# TEMPIC.net
KiCad netlist of a schematic drawn in Altium Designer
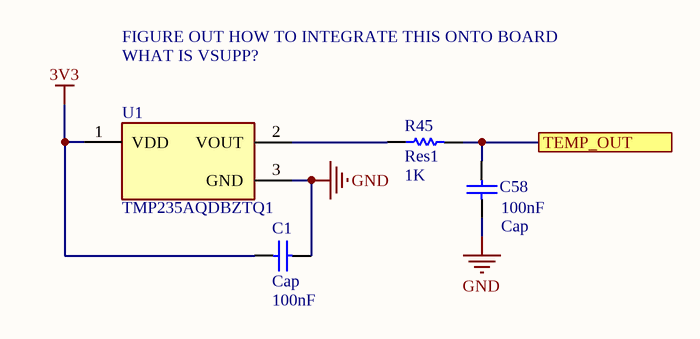
[diagram p0: TEMPIC.SchDoc]

(export (version "E")
  (design (tool "Eeschema 10.0.6"))
  (components
    (comp (ref "C1")
      (value "Cap")
      (footprint "0402")
      (description "Capacitor")
      (fields (field (name "ALTIUM_VALUE") "100nF") (field (name "PUBLISHER") "Altium Limited"))
      (libsource (lib "Miscellaneous Devices") (part "Cap"))
    )
    (comp (ref "C58")
      (value "Cap")
      (footprint "0402")
      (description "Capacitor")
      (fields (field (name "ALTIUM_VALUE") "100nF") (field (name "PUBLISHER") "Altium Limited"))
      (libsource (lib "Miscellaneous Devices") (part "Cap"))
    )
    (comp (ref "R45")
      (value "Res1")
      (footprint "0402")
      (description "Resistor")
      (fields (field (name "ALTIUM_VALUE") "1K") (field (name "PUBLISHER") "Altium Limited"))
      (libsource (lib "Miscellaneous Devices") (part "Res1"))
    )
    (comp (ref "U1")
      (value "TMP235AQDBZTQ1")
      (footprint "FP-DBZ0003A-MFG")
      (description "LOW-POWER HIGH-ACCURACY ANALOG O")
      (fields
        (field (name "MANUFACTURER") "Texas Instruments")
        (field (name "MANUFACTURER PART NUMBER") "TMP235A2DBZR")
      )
      (libsource (lib "Altium Content Vault") (part "1212246baba8f64ab0dd7b63bd818eb"))
    )
  )
  (nets
    (net (code "1") (name "/TEMP_OUT") (class "Default")
      (node (ref "C58") (pin "1") (pinfunction "1_1") (pintype "passive"))
      (node (ref "R45") (pin "2") (pinfunction "2_2") (pintype "passive"))
    )
    (net (code "2") (name "3V3") (class "Default")
      (node (ref "C1") (pin "1") (pinfunction "1_1") (pintype "passive"))
      (node (ref "U1") (pin "1") (pinfunction "VDD_1") (pintype "power_in"))
    )
    (net (code "3") (name "GND") (class "Default")
      (node (ref "C1") (pin "2") (pinfunction "2_2") (pintype "passive"))
      (node (ref "C58") (pin "2") (pinfunction "2_2") (pintype "passive"))
      (node (ref "U1") (pin "3") (pinfunction "GND_3") (pintype "power_in"))
    )
    (net (code "4") (name "Net-(U1-VOUT)") (class "Default")
      (node (ref "R45") (pin "1") (pinfunction "1_1") (pintype "passive"))
      (node (ref "U1") (pin "2") (pinfunction "VOUT_2") (pintype "passive"))
    )
  )
)
